# Sensor_Board.net
KiCad netlist of a schematic drawn in EAGLE
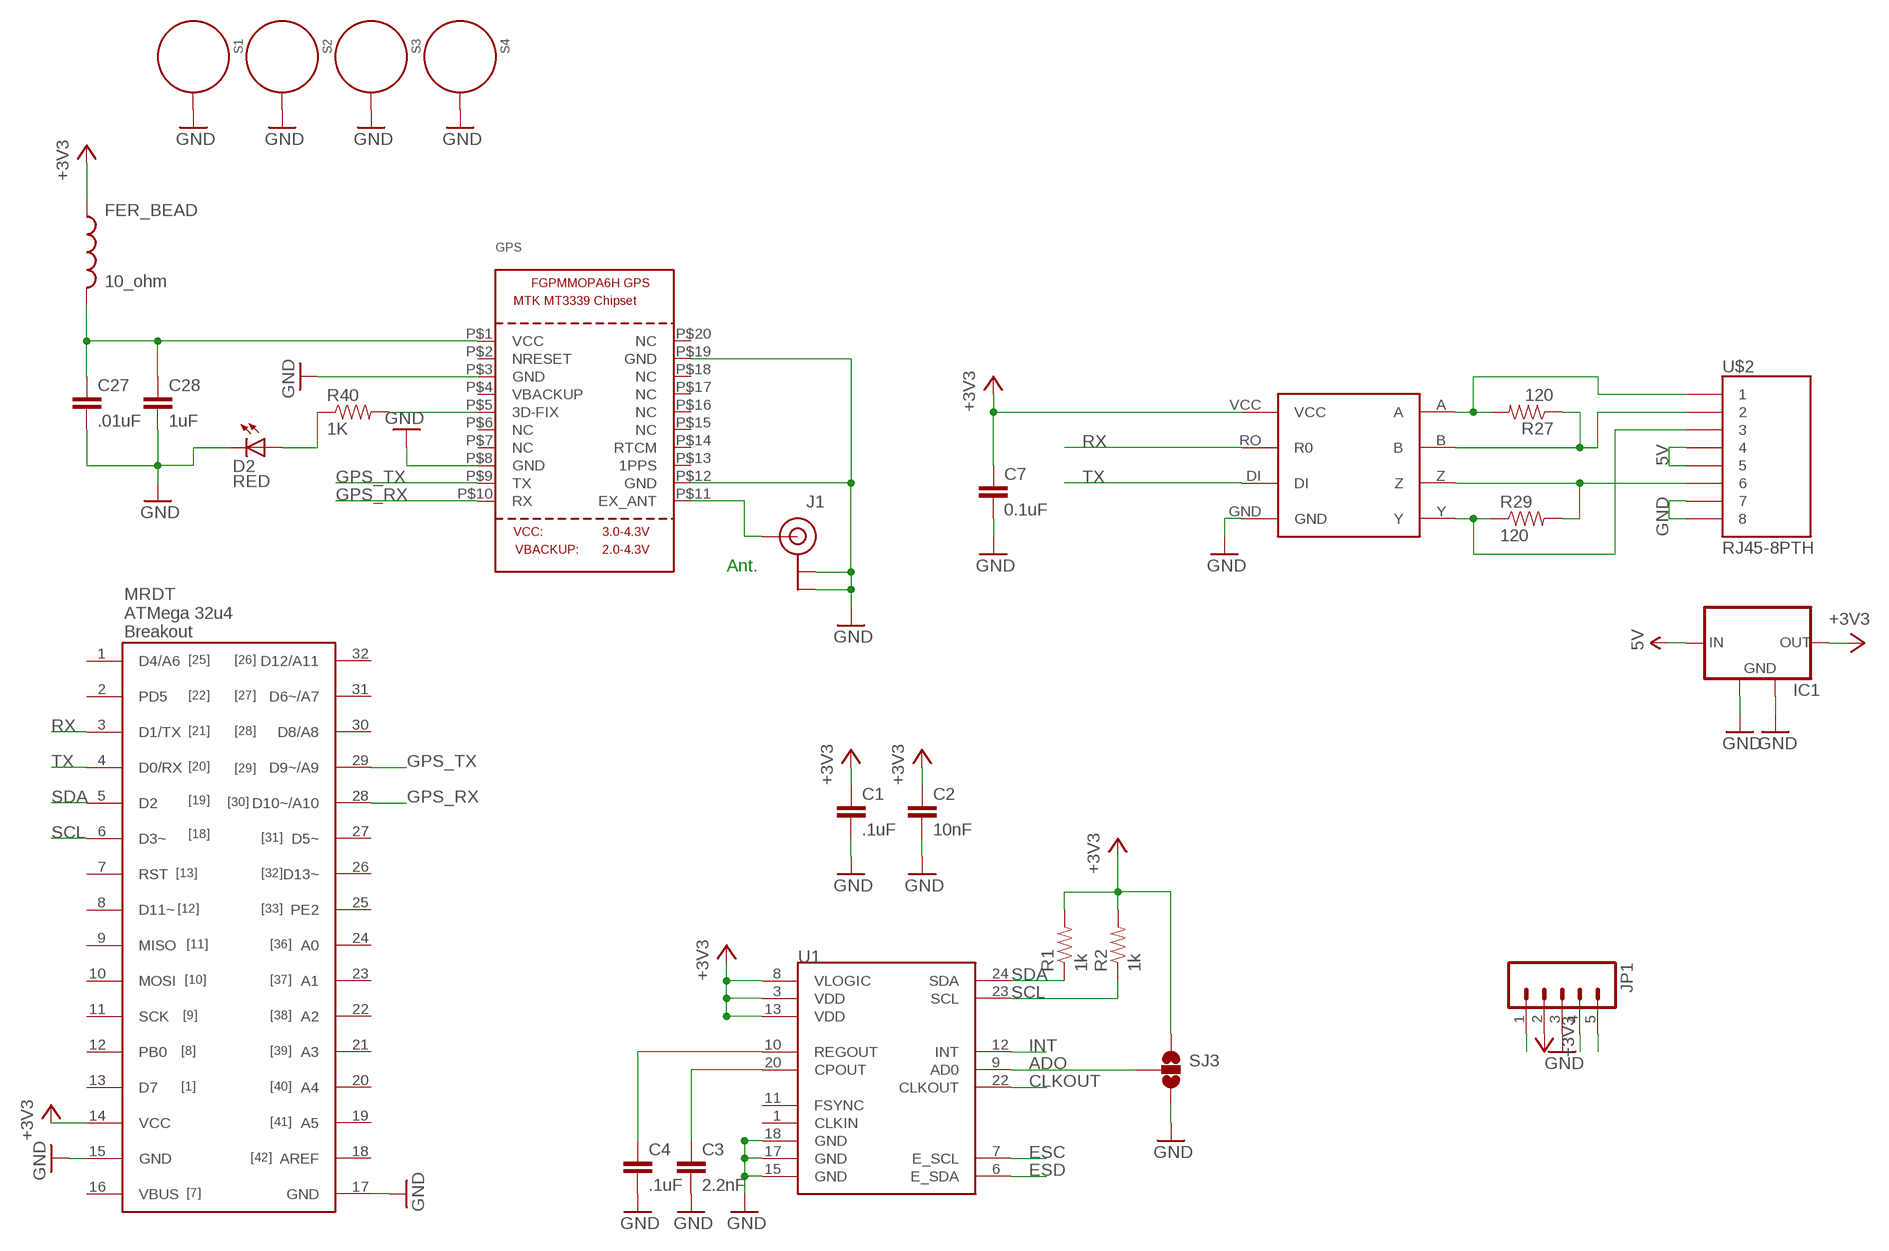
[diagram p0: schematic, sheet 1]

(export (version "E")
  (design (tool "Eeschema 10.0.6"))
  (components
    (comp (ref "C1")
      (value ".1uF")
      (footprint "eagle-import:1206")
      (libsource (lib "eagle-import") (part "CAP1206"))
    )
    (comp (ref "C2")
      (value "10nF")
      (footprint "eagle-import:1206")
      (libsource (lib "eagle-import") (part "CAP1206"))
    )
    (comp (ref "C3")
      (value "2.2nF")
      (footprint "eagle-import:1206")
      (libsource (lib "eagle-import") (part "CAP1206"))
    )
    (comp (ref "C4")
      (value ".1uF")
      (footprint "eagle-import:1206")
      (libsource (lib "eagle-import") (part "CAP1206"))
    )
    (comp (ref "C7")
      (value "0.1uF")
      (footprint "eagle-import:1206")
      (libsource (lib "eagle-import") (part "SparkFun-Passives_CAP1206"))
    )
    (comp (ref "C27")
      (value ".01uF")
      (footprint "eagle-import:1206")
      (libsource (lib "eagle-import") (part "SparkFun-Passives_CAP1206"))
    )
    (comp (ref "C28")
      (value "1uF")
      (footprint "eagle-import:1206")
      (libsource (lib "eagle-import") (part "SparkFun-Passives_CAP1206"))
    )
    (comp (ref "D2")
      (value "RED")
      (footprint "eagle-import:LED-1206")
      (libsource (lib "eagle-import") (part "LED-RED1206"))
    )
    (comp (ref "FER_BEAD")
      (value "10_ohm")
      (footprint "eagle-import:0603")
      (libsource (lib "eagle-import") (part "INDUCTOR30OHM,1.8A"))
    )
    (comp (ref "GPS")
      (value "GPS_FGPMMOPA6H")
      (footprint "eagle-import:FGPMMOPA6H")
      (libsource (lib "eagle-import") (part "GPS_FGPMMOPA6H"))
    )
    (comp (ref "IC1")
      (value "MCP1825S-SOT223")
      (footprint "eagle-import:SOT223")
      (libsource (lib "eagle-import") (part "MCP1825S-SOT223"))
    )
    (comp (ref "J1")
      (value "U.FL")
      (footprint "eagle-import:U.FL")
      (libsource (lib "eagle-import") (part "U.FL"))
    )
    (comp (ref "JP1")
      (value "M05PTH")
      (footprint "eagle-import:1X05")
      (libsource (lib "eagle-import") (part "M05PTH"))
    )
    (comp (ref "R1")
      (value "1k")
      (footprint "eagle-import:1206")
      (libsource (lib "eagle-import") (part "SparkFun-Resistors_RESISTOR1206"))
    )
    (comp (ref "R2")
      (value "1k")
      (footprint "eagle-import:1206")
      (libsource (lib "eagle-import") (part "SparkFun-Resistors_RESISTOR1206"))
    )
    (comp (ref "R27")
      (value "120")
      (footprint "eagle-import:1206")
      (libsource (lib "eagle-import") (part "RESISTOR1206"))
    )
    (comp (ref "R29")
      (value "120")
      (footprint "eagle-import:1206")
      (libsource (lib "eagle-import") (part "RESISTOR1206"))
    )
    (comp (ref "R40")
      (value "1K")
      (footprint "eagle-import:1206")
      (libsource (lib "eagle-import") (part "RESISTOR1206"))
    )
    (comp (ref "RS-485-2")
      (value "MAX3077")
      (footprint "eagle-import:MAX3070E")
      (libsource (lib "eagle-import") (part "MAX3077"))
    )
    (comp (ref "S1")
      (value "STANDOFF_ELECTRICAL")
      (footprint "eagle-import:STANDOFF-ELECTRICAL")
      (libsource (lib "eagle-import") (part "STANDOFF_ELECTRICAL"))
    )
    (comp (ref "S2")
      (value "STANDOFF_ELECTRICAL")
      (footprint "eagle-import:STANDOFF-ELECTRICAL")
      (libsource (lib "eagle-import") (part "STANDOFF_ELECTRICAL"))
    )
    (comp (ref "S3")
      (value "STANDOFF_ELECTRICAL")
      (footprint "eagle-import:STANDOFF-ELECTRICAL")
      (libsource (lib "eagle-import") (part "STANDOFF_ELECTRICAL"))
    )
    (comp (ref "S4")
      (value "STANDOFF_ELECTRICAL")
      (footprint "eagle-import:STANDOFF-ELECTRICAL")
      (libsource (lib "eagle-import") (part "STANDOFF_ELECTRICAL"))
    )
    (comp (ref "SJ3")
      (value "SOLDERJUMPER_2WAYS")
      (footprint "eagle-import:SJ_3")
      (libsource (lib "eagle-import") (part "SOLDERJUMPER_2WAYS"))
    )
    (comp (ref "U$1")
      (value "32U4_BREAKOUT")
      (footprint "eagle-import:32U4_MCU_DIP")
      (libsource (lib "eagle-import") (part "32U4_BREAKOUT"))
    )
    (comp (ref "U$2")
      (value "RJ45-8PTH")
      (footprint "eagle-import:RJ45-8")
      (libsource (lib "eagle-import") (part "RJ45-8PTH"))
    )
    (comp (ref "U1")
      (value "MPU-9150QFN-24-NP")
      (footprint "eagle-import:QFN-24-NP")
      (libsource (lib "eagle-import") (part "MPU-9150QFN-24-NP"))
    )
  )
  (nets
    (net (code "1") (name "+3V3") (class "Default")
      (node (ref "C1") (pin "1") (pinfunction "1_1") (pintype "passive"))
      (node (ref "C2") (pin "1") (pinfunction "1_1") (pintype "passive"))
      (node (ref "C7") (pin "1") (pinfunction "1_1") (pintype "passive"))
      (node (ref "FER_BEAD") (pin "1") (pinfunction "1_1") (pintype "passive"))
      (node (ref "IC1") (pin "3") (pinfunction "OUT_3") (pintype "output"))
      (node (ref "JP1") (pin "2") (pinfunction "2_2") (pintype "passive"))
      (node (ref "R1") (pin "2") (pinfunction "2_2") (pintype "passive"))
      (node (ref "R2") (pin "2") (pinfunction "2_2") (pintype "passive"))
      (node (ref "RS-485-2") (pin "VCC") (pinfunction "VCC_VCC") (pintype "bidirectional"))
      (node (ref "SJ3") (pin "1") (pinfunction "1_1") (pintype "passive"))
      (node (ref "U$1") (pin "14") (pinfunction "VCC_14") (pintype "bidirectional"))
      (node (ref "U1") (pin "13") (pinfunction "VDD_13") (pintype "bidirectional"))
      (node (ref "U1") (pin "3") (pinfunction "VDD_3") (pintype "bidirectional"))
      (node (ref "U1") (pin "8") (pinfunction "VLOGIC_8") (pintype "bidirectional"))
    )
    (net (code "2") (name "/ADO") (class "Default")
      (node (ref "SJ3") (pin "2") (pinfunction "2_2") (pintype "passive"))
      (node (ref "U1") (pin "9") (pinfunction "AD0_9") (pintype "bidirectional"))
    )
    (net (code "3") (name "/CLKOUT") (class "Default")
      (node (ref "U1") (pin "22") (pinfunction "CLKOUT_22") (pintype "bidirectional"))
    )
    (net (code "4") (name "/ESC") (class "Default")
      (node (ref "U1") (pin "7") (pinfunction "E_SCL_7") (pintype "bidirectional"))
    )
    (net (code "5") (name "/ESD") (class "Default")
      (node (ref "U1") (pin "6") (pinfunction "E_SDA_6") (pintype "bidirectional"))
    )
    (net (code "6") (name "/GPS_RX") (class "Default")
      (node (ref "GPS") (pin "P$10") (pinfunction "RX_P$10") (pintype "bidirectional"))
      (node (ref "U$1") (pin "28") (pinfunction "D10~{/A10}_28") (pintype "bidirectional"))
    )
    (net (code "7") (name "/GPS_TX") (class "Default")
      (node (ref "GPS") (pin "P$9") (pinfunction "TX_P$9") (pintype "bidirectional"))
      (node (ref "U$1") (pin "29") (pinfunction "D9~{/A9}_29") (pintype "bidirectional"))
    )
    (net (code "8") (name "/INT") (class "Default")
      (node (ref "U1") (pin "12") (pinfunction "INT_12") (pintype "bidirectional"))
    )
    (net (code "9") (name "/RX") (class "Default")
      (node (ref "RS-485-2") (pin "RO") (pinfunction "R0_RO") (pintype "bidirectional"))
      (node (ref "U$1") (pin "3") (pinfunction "D1/TX_3") (pintype "bidirectional"))
    )
    (net (code "10") (name "/SCL") (class "Default")
      (node (ref "JP1") (pin "4") (pinfunction "4_4") (pintype "passive"))
      (node (ref "R2") (pin "1") (pinfunction "1_1") (pintype "passive"))
      (node (ref "U$1") (pin "6") (pinfunction "D3~{}_6") (pintype "bidirectional"))
      (node (ref "U1") (pin "23") (pinfunction "SCL_23") (pintype "bidirectional"))
    )
    (net (code "11") (name "/SDA") (class "Default")
      (node (ref "JP1") (pin "5") (pinfunction "5_5") (pintype "passive"))
      (node (ref "R1") (pin "1") (pinfunction "1_1") (pintype "passive"))
      (node (ref "U$1") (pin "5") (pinfunction "D2_5") (pintype "bidirectional"))
      (node (ref "U1") (pin "24") (pinfunction "SDA_24") (pintype "bidirectional"))
    )
    (net (code "12") (name "/TX") (class "Default")
      (node (ref "RS-485-2") (pin "DI") (pinfunction "DI_DI") (pintype "bidirectional"))
      (node (ref "U$1") (pin "4") (pinfunction "D0/RX_4") (pintype "bidirectional"))
    )
    (net (code "13") (name "5V") (class "Default")
      (node (ref "IC1") (pin "1") (pinfunction "IN_1") (pintype "input"))
      (node (ref "U$2") (pin "4") (pinfunction "4_4") (pintype "bidirectional"))
      (node (ref "U$2") (pin "5") (pinfunction "5_5") (pintype "bidirectional"))
    )
    (net (code "14") (name "GND") (class "Default")
      (node (ref "C1") (pin "2") (pinfunction "2_2") (pintype "passive"))
      (node (ref "C2") (pin "2") (pinfunction "2_2") (pintype "passive"))
      (node (ref "C27") (pin "2") (pinfunction "2_2") (pintype "passive"))
      (node (ref "C28") (pin "2") (pinfunction "2_2") (pintype "passive"))
      (node (ref "C3") (pin "2") (pinfunction "2_2") (pintype "passive"))
      (node (ref "C4") (pin "2") (pinfunction "2_2") (pintype "passive"))
      (node (ref "C7") (pin "2") (pinfunction "2_2") (pintype "passive"))
      (node (ref "D2") (pin "C") (pinfunction "C_C") (pintype "passive"))
      (node (ref "GPS") (pin "P$12") (pinfunction "GND_P$12") (pintype "bidirectional"))
      (node (ref "GPS") (pin "P$19") (pinfunction "GND_P$19") (pintype "bidirectional"))
      (node (ref "GPS") (pin "P$3") (pinfunction "GND_P$3") (pintype "bidirectional"))
      (node (ref "GPS") (pin "P$8") (pinfunction "GND_P$8") (pintype "bidirectional"))
      (node (ref "IC1") (pin "2") (pinfunction "GND_2") (pintype "power_in"))
      (node (ref "IC1") (pin "4") (pinfunction "GND_4") (pintype "power_in"))
      (node (ref "J1") (pin "P$1") (pinfunction "GND_P$1") (pintype "bidirectional"))
      (node (ref "J1") (pin "P$2") (pinfunction "GND_P$2") (pintype "bidirectional"))
      (node (ref "JP1") (pin "3") (pinfunction "3_3") (pintype "passive"))
      (node (ref "RS-485-2") (pin "GND") (pinfunction "GND_GND") (pintype "bidirectional"))
      (node (ref "S1") (pin "P1") (pinfunction "P$1_P1") (pintype "bidirectional"))
      (node (ref "S2") (pin "P1") (pinfunction "P$1_P1") (pintype "bidirectional"))
      (node (ref "S3") (pin "P1") (pinfunction "P$1_P1") (pintype "bidirectional"))
      (node (ref "S4") (pin "P1") (pinfunction "P$1_P1") (pintype "bidirectional"))
      (node (ref "SJ3") (pin "3") (pinfunction "3_3") (pintype "passive"))
      (node (ref "U$1") (pin "15") (pinfunction "GND_15") (pintype "bidirectional"))
      (node (ref "U$1") (pin "17") (pinfunction "GND_17") (pintype "bidirectional"))
      (node (ref "U$2") (pin "7") (pinfunction "7_7") (pintype "bidirectional"))
      (node (ref "U$2") (pin "8") (pinfunction "8_8") (pintype "bidirectional"))
      (node (ref "U1") (pin "15") (pinfunction "GND_15") (pintype "bidirectional"))
      (node (ref "U1") (pin "17") (pinfunction "GND_17") (pintype "bidirectional"))
      (node (ref "U1") (pin "18") (pinfunction "GND_18") (pintype "bidirectional"))
    )
    (net (code "15") (name "Net-(D2-PadA)") (class "Default")
      (node (ref "D2") (pin "A") (pinfunction "A_A") (pintype "passive"))
      (node (ref "R40") (pin "1") (pinfunction "1_1") (pintype "passive"))
    )
    (net (code "16") (name "Net-(GPS-3D-FIX)") (class "Default")
      (node (ref "GPS") (pin "P$5") (pinfunction "3D-FIX_P$5") (pintype "bidirectional"))
      (node (ref "R40") (pin "2") (pinfunction "2_2") (pintype "passive"))
    )
    (net (code "17") (name "Net-(GPS-EX_ANT)") (class "Default")
      (node (ref "GPS") (pin "P$11") (pinfunction "EX_ANT_P$11") (pintype "bidirectional"))
      (node (ref "J1") (pin "P$3") (pinfunction "SIGNAL_P$3") (pintype "bidirectional"))
    )
    (net (code "18") (name "Net-(GPS-VCC)") (class "Default")
      (node (ref "C27") (pin "1") (pinfunction "1_1") (pintype "passive"))
      (node (ref "C28") (pin "1") (pinfunction "1_1") (pintype "passive"))
      (node (ref "FER_BEAD") (pin "2") (pinfunction "2_2") (pintype "passive"))
      (node (ref "GPS") (pin "P$1") (pinfunction "VCC_P$1") (pintype "bidirectional"))
    )
    (net (code "19") (name "Net-(R27-Pad1)") (class "Default")
      (node (ref "R27") (pin "1") (pinfunction "1_1") (pintype "passive"))
      (node (ref "RS-485-2") (pin "B") (pinfunction "B_B") (pintype "bidirectional"))
      (node (ref "U$2") (pin "2") (pinfunction "2_2") (pintype "bidirectional"))
    )
    (net (code "20") (name "Net-(R27-Pad2)") (class "Default")
      (node (ref "R27") (pin "2") (pinfunction "2_2") (pintype "passive"))
      (node (ref "RS-485-2") (pin "A") (pinfunction "A_A") (pintype "bidirectional"))
      (node (ref "U$2") (pin "1") (pinfunction "1_1") (pintype "bidirectional"))
    )
    (net (code "21") (name "Net-(R29-Pad1)") (class "Default")
      (node (ref "R29") (pin "1") (pinfunction "1_1") (pintype "passive"))
      (node (ref "RS-485-2") (pin "Y") (pinfunction "Y_Y") (pintype "bidirectional"))
      (node (ref "U$2") (pin "3") (pinfunction "3_3") (pintype "bidirectional"))
    )
    (net (code "22") (name "Net-(R29-Pad2)") (class "Default")
      (node (ref "R29") (pin "2") (pinfunction "2_2") (pintype "passive"))
      (node (ref "RS-485-2") (pin "Z") (pinfunction "Z_Z") (pintype "bidirectional"))
      (node (ref "U$2") (pin "6") (pinfunction "6_6") (pintype "bidirectional"))
    )
    (net (code "23") (name "Net-(U1-CPOUT)") (class "Default")
      (node (ref "C3") (pin "1") (pinfunction "1_1") (pintype "passive"))
      (node (ref "U1") (pin "20") (pinfunction "CPOUT_20") (pintype "bidirectional"))
    )
    (net (code "24") (name "Net-(U1-REGOUT)") (class "Default")
      (node (ref "C4") (pin "1") (pinfunction "1_1") (pintype "passive"))
      (node (ref "U1") (pin "10") (pinfunction "REGOUT_10") (pintype "bidirectional"))
    )
    (net (code "25") (name "unconnected-(GPS-1PPS-PadP$13)") (class "Default")
      (node (ref "GPS") (pin "P$13") (pinfunction "1PPS_P$13") (pintype "bidirectional"))
    )
    (net (code "26") (name "unconnected-(GPS-NC-PadP$6)") (class "Default")
      (node (ref "GPS") (pin "P$6") (pinfunction "NC_P$6") (pintype "bidirectional"))
    )
    (net (code "27") (name "unconnected-(GPS-NC-PadP$7)") (class "Default")
      (node (ref "GPS") (pin "P$7") (pinfunction "NC_P$7") (pintype "bidirectional"))
    )
    (net (code "28") (name "unconnected-(GPS-NC-PadP$15)") (class "Default")
      (node (ref "GPS") (pin "P$15") (pinfunction "NC_P$15") (pintype "bidirectional"))
    )
    (net (code "29") (name "unconnected-(GPS-NC-PadP$16)") (class "Default")
      (node (ref "GPS") (pin "P$16") (pinfunction "NC_P$16") (pintype "bidirectional"))
    )
    (net (code "30") (name "unconnected-(GPS-NC-PadP$17)") (class "Default")
      (node (ref "GPS") (pin "P$17") (pinfunction "NC_P$17") (pintype "bidirectional"))
    )
    (net (code "31") (name "unconnected-(GPS-NC-PadP$18)") (class "Default")
      (node (ref "GPS") (pin "P$18") (pinfunction "NC_P$18") (pintype "bidirectional"))
    )
    (net (code "32") (name "unconnected-(GPS-NC-PadP$20)") (class "Default")
      (node (ref "GPS") (pin "P$20") (pinfunction "NC_P$20") (pintype "bidirectional"))
    )
    (net (code "33") (name "unconnected-(GPS-NRESET-PadP$2)") (class "Default")
      (node (ref "GPS") (pin "P$2") (pinfunction "NRESET_P$2") (pintype "bidirectional"))
    )
    (net (code "34") (name "unconnected-(GPS-RTCM-PadP$14)") (class "Default")
      (node (ref "GPS") (pin "P$14") (pinfunction "RTCM_P$14") (pintype "bidirectional"))
    )
    (net (code "35") (name "unconnected-(GPS-VBACKUP-PadP$4)") (class "Default")
      (node (ref "GPS") (pin "P$4") (pinfunction "VBACKUP_P$4") (pintype "bidirectional"))
    )
    (net (code "36") (name "unconnected-(JP1-Pad1)") (class "Default")
      (node (ref "JP1") (pin "1") (pinfunction "1_1") (pintype "passive"))
    )
    (net (code "37") (name "unconnected-(U$1-A0-Pad24)") (class "Default")
      (node (ref "U$1") (pin "24") (pinfunction "A0_24") (pintype "bidirectional"))
    )
    (net (code "38") (name "unconnected-(U$1-A1-Pad23)") (class "Default")
      (node (ref "U$1") (pin "23") (pinfunction "A1_23") (pintype "bidirectional"))
    )
    (net (code "39") (name "unconnected-(U$1-A2-Pad22)") (class "Default")
      (node (ref "U$1") (pin "22") (pinfunction "A2_22") (pintype "bidirectional"))
    )
    (net (code "40") (name "unconnected-(U$1-A3-Pad21)") (class "Default")
      (node (ref "U$1") (pin "21") (pinfunction "A3_21") (pintype "bidirectional"))
    )
    (net (code "41") (name "unconnected-(U$1-A4-Pad20)") (class "Default")
      (node (ref "U$1") (pin "20") (pinfunction "A4_20") (pintype "bidirectional"))
    )
    (net (code "42") (name "unconnected-(U$1-A5-Pad19)") (class "Default")
      (node (ref "U$1") (pin "19") (pinfunction "A5_19") (pintype "bidirectional"))
    )
    (net (code "43") (name "unconnected-(U$1-AREF-Pad18)") (class "Default")
      (node (ref "U$1") (pin "18") (pinfunction "AREF_18") (pintype "bidirectional"))
    )
    (net (code "44") (name "unconnected-(U$1-D4{slash}A6-Pad1)") (class "Default")
      (node (ref "U$1") (pin "1") (pinfunction "D4/A6_1") (pintype "bidirectional"))
    )
    (net (code "45") (name "unconnected-(U$1-D5~{}-Pad27)") (class "Default")
      (node (ref "U$1") (pin "27") (pinfunction "D5~{}_27") (pintype "bidirectional"))
    )
    (net (code "46") (name "unconnected-(U$1-D6~{{slash}A7}-Pad31)") (class "Default")
      (node (ref "U$1") (pin "31") (pinfunction "D6~{/A7}_31") (pintype "bidirectional"))
    )
    (net (code "47") (name "unconnected-(U$1-D7-Pad13)") (class "Default")
      (node (ref "U$1") (pin "13") (pinfunction "D7_13") (pintype "bidirectional"))
    )
    (net (code "48") (name "unconnected-(U$1-D8{slash}A8-Pad30)") (class "Default")
      (node (ref "U$1") (pin "30") (pinfunction "D8/A8_30") (pintype "bidirectional"))
    )
    (net (code "49") (name "unconnected-(U$1-D11~{}-Pad8)") (class "Default")
      (node (ref "U$1") (pin "8") (pinfunction "D11~{}_8") (pintype "bidirectional"))
    )
    (net (code "50") (name "unconnected-(U$1-D12{slash}A11-Pad32)") (class "Default")
      (node (ref "U$1") (pin "32") (pinfunction "D12/A11_32") (pintype "bidirectional"))
    )
    (net (code "51") (name "unconnected-(U$1-D13~{}-Pad26)") (class "Default")
      (node (ref "U$1") (pin "26") (pinfunction "D13~{}_26") (pintype "bidirectional"))
    )
    (net (code "52") (name "unconnected-(U$1-MISO-Pad9)") (class "Default")
      (node (ref "U$1") (pin "9") (pinfunction "MISO_9") (pintype "bidirectional"))
    )
    (net (code "53") (name "unconnected-(U$1-MOSI-Pad10)") (class "Default")
      (node (ref "U$1") (pin "10") (pinfunction "MOSI_10") (pintype "bidirectional"))
    )
    (net (code "54") (name "unconnected-(U$1-PB0-Pad12)") (class "Default")
      (node (ref "U$1") (pin "12") (pinfunction "PB0_12") (pintype "bidirectional"))
    )
    (net (code "55") (name "unconnected-(U$1-PD5-Pad2)") (class "Default")
      (node (ref "U$1") (pin "2") (pinfunction "PD5_2") (pintype "bidirectional"))
    )
    (net (code "56") (name "unconnected-(U$1-PE2-Pad25)") (class "Default")
      (node (ref "U$1") (pin "25") (pinfunction "PE2_25") (pintype "bidirectional"))
    )
    (net (code "57") (name "unconnected-(U$1-RST-Pad7)") (class "Default")
      (node (ref "U$1") (pin "7") (pinfunction "RST_7") (pintype "bidirectional"))
    )
    (net (code "58") (name "unconnected-(U$1-SCK-Pad11)") (class "Default")
      (node (ref "U$1") (pin "11") (pinfunction "SCK_11") (pintype "bidirectional"))
    )
    (net (code "59") (name "unconnected-(U$1-VBUS-Pad16)") (class "Default")
      (node (ref "U$1") (pin "16") (pinfunction "VBUS_16") (pintype "bidirectional"))
    )
    (net (code "60") (name "unconnected-(U1-CLKIN-Pad1)") (class "Default")
      (node (ref "U1") (pin "1") (pinfunction "CLKIN_1") (pintype "bidirectional"))
    )
    (net (code "61") (name "unconnected-(U1-FSYNC-Pad11)") (class "Default")
      (node (ref "U1") (pin "11") (pinfunction "FSYNC_11") (pintype "bidirectional"))
    )
  )
)
